# A80R_EQ_Repro.net
KiCad netlist of a schematic drawn in Altium Designer
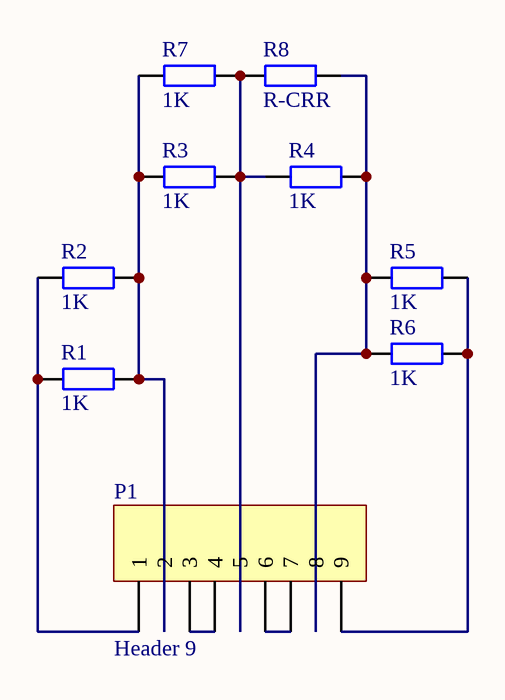
[diagram p0: A80R_EQ_Repro.SchDoc]

(export (version "E")
  (design (tool "Eeschema 10.0.6"))
  (components
    (comp (ref "P1")
      (value "Header 9")
      (footprint "HDR1X9")
      (description "Header, 9-Pin")
      (fields (field (name "PUBLISHER") "Altium Limited"))
      (libsource (lib "Connectors") (part "Header 9"))
    )
    (comp (ref "R1")
      (value "1K")
      (footprint "RS 1/4W")
      (description "直插色环电阻")
      (fields (field (name "版权归属") "源创客"))
      (libsource (lib "电阻-电容-电感") (part "R-CRR"))
    )
    (comp (ref "R2")
      (value "1K")
      (footprint "RS 1/4W")
      (description "直插色环电阻")
      (fields (field (name "版权归属") "源创客"))
      (libsource (lib "电阻-电容-电感") (part "R-CRR"))
    )
    (comp (ref "R3")
      (value "1K")
      (footprint "RS 1/4W")
      (description "直插色环电阻")
      (fields (field (name "版权归属") "源创客"))
      (libsource (lib "电阻-电容-电感") (part "R-CRR"))
    )
    (comp (ref "R4")
      (value "1K")
      (footprint "RS 1/4W")
      (description "直插色环电阻")
      (fields (field (name "版权归属") "源创客"))
      (libsource (lib "电阻-电容-电感") (part "R-CRR"))
    )
    (comp (ref "R5")
      (value "1K")
      (footprint "RS 1/4W")
      (description "直插色环电阻")
      (fields (field (name "版权归属") "源创客"))
      (libsource (lib "电阻-电容-电感") (part "R-CRR"))
    )
    (comp (ref "R6")
      (value "1K")
      (footprint "RS 1/4W")
      (description "直插色环电阻")
      (fields (field (name "版权归属") "源创客"))
      (libsource (lib "电阻-电容-电感") (part "R-CRR"))
    )
    (comp (ref "R7")
      (value "1K")
      (footprint "RS 1/2W-L")
      (description "直插色环电阻")
      (fields (field (name "版权归属") "源创客"))
      (libsource (lib "电阻-电容-电感") (part "R-CRR"))
    )
    (comp (ref "R8")
      (value "R-CRR")
      (footprint "RS 1/2W-L")
      (description "直插色环电阻")
      (fields (field (name "版权归属") "源创客"))
      (libsource (lib "电阻-电容-电感") (part "R-CRR"))
    )
  )
  (nets
    (net (code "1") (name "Net-(P1-Pad1)") (class "Default")
      (node (ref "P1") (pin "1") (pinfunction "1_1") (pintype "passive"))
      (node (ref "R1") (pin "1") (pinfunction "1_1") (pintype "passive"))
      (node (ref "R2") (pin "1") (pinfunction "1_1") (pintype "passive"))
    )
    (net (code "2") (name "Net-(P1-Pad2)") (class "Default")
      (node (ref "P1") (pin "2") (pinfunction "2_2") (pintype "passive"))
      (node (ref "R1") (pin "2") (pinfunction "2_2") (pintype "passive"))
      (node (ref "R2") (pin "2") (pinfunction "2_2") (pintype "passive"))
      (node (ref "R3") (pin "1") (pinfunction "1_1") (pintype "passive"))
      (node (ref "R7") (pin "1") (pinfunction "1_1") (pintype "passive"))
    )
    (net (code "3") (name "Net-(P1-Pad3)") (class "Default")
      (node (ref "P1") (pin "3") (pinfunction "3_3") (pintype "passive"))
      (node (ref "P1") (pin "4") (pinfunction "4_4") (pintype "passive"))
    )
    (net (code "4") (name "Net-(P1-Pad5)") (class "Default")
      (node (ref "P1") (pin "5") (pinfunction "5_5") (pintype "passive"))
      (node (ref "R3") (pin "2") (pinfunction "2_2") (pintype "passive"))
      (node (ref "R4") (pin "1") (pinfunction "1_1") (pintype "passive"))
      (node (ref "R7") (pin "2") (pinfunction "2_2") (pintype "passive"))
      (node (ref "R8") (pin "1") (pinfunction "1_1") (pintype "passive"))
    )
    (net (code "5") (name "Net-(P1-Pad6)") (class "Default")
      (node (ref "P1") (pin "6") (pinfunction "6_6") (pintype "passive"))
      (node (ref "P1") (pin "7") (pinfunction "7_7") (pintype "passive"))
    )
    (net (code "6") (name "Net-(P1-Pad8)") (class "Default")
      (node (ref "P1") (pin "8") (pinfunction "8_8") (pintype "passive"))
      (node (ref "R4") (pin "2") (pinfunction "2_2") (pintype "passive"))
      (node (ref "R5") (pin "1") (pinfunction "1_1") (pintype "passive"))
      (node (ref "R6") (pin "1") (pinfunction "1_1") (pintype "passive"))
      (node (ref "R8") (pin "2") (pinfunction "2_2") (pintype "passive"))
    )
    (net (code "7") (name "Net-(P1-Pad9)") (class "Default")
      (node (ref "P1") (pin "9") (pinfunction "9_9") (pintype "passive"))
      (node (ref "R5") (pin "2") (pinfunction "2_2") (pintype "passive"))
      (node (ref "R6") (pin "2") (pinfunction "2_2") (pintype "passive"))
    )
  )
)
